# ENERGIS-Display-Board-1_1_0.net
KiCad netlist of a schematic drawn in EAGLE
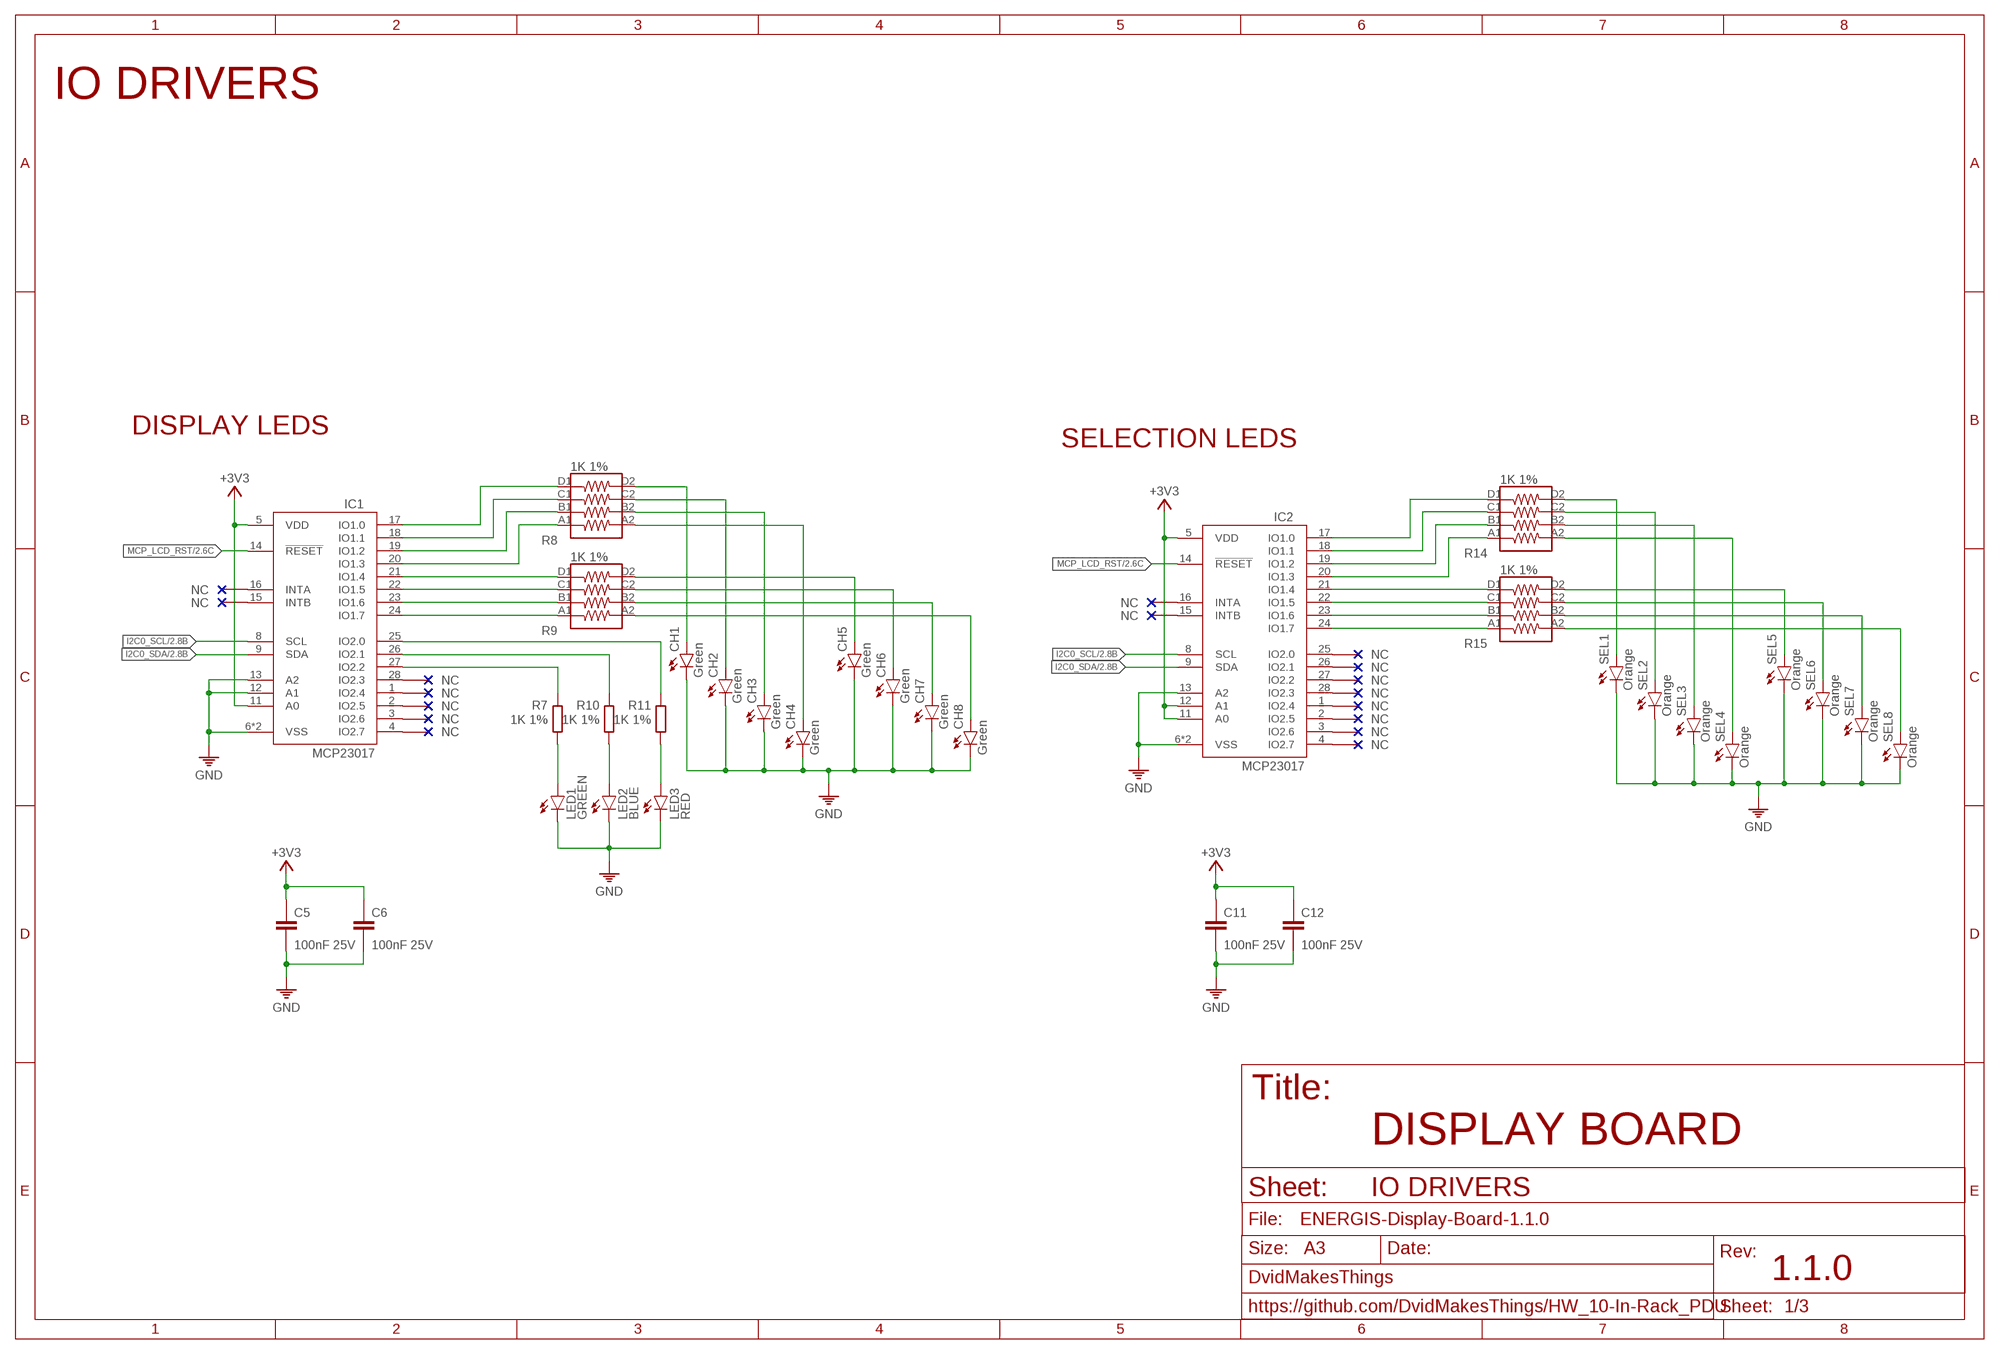
[diagram p0: schematic, sheet 1]
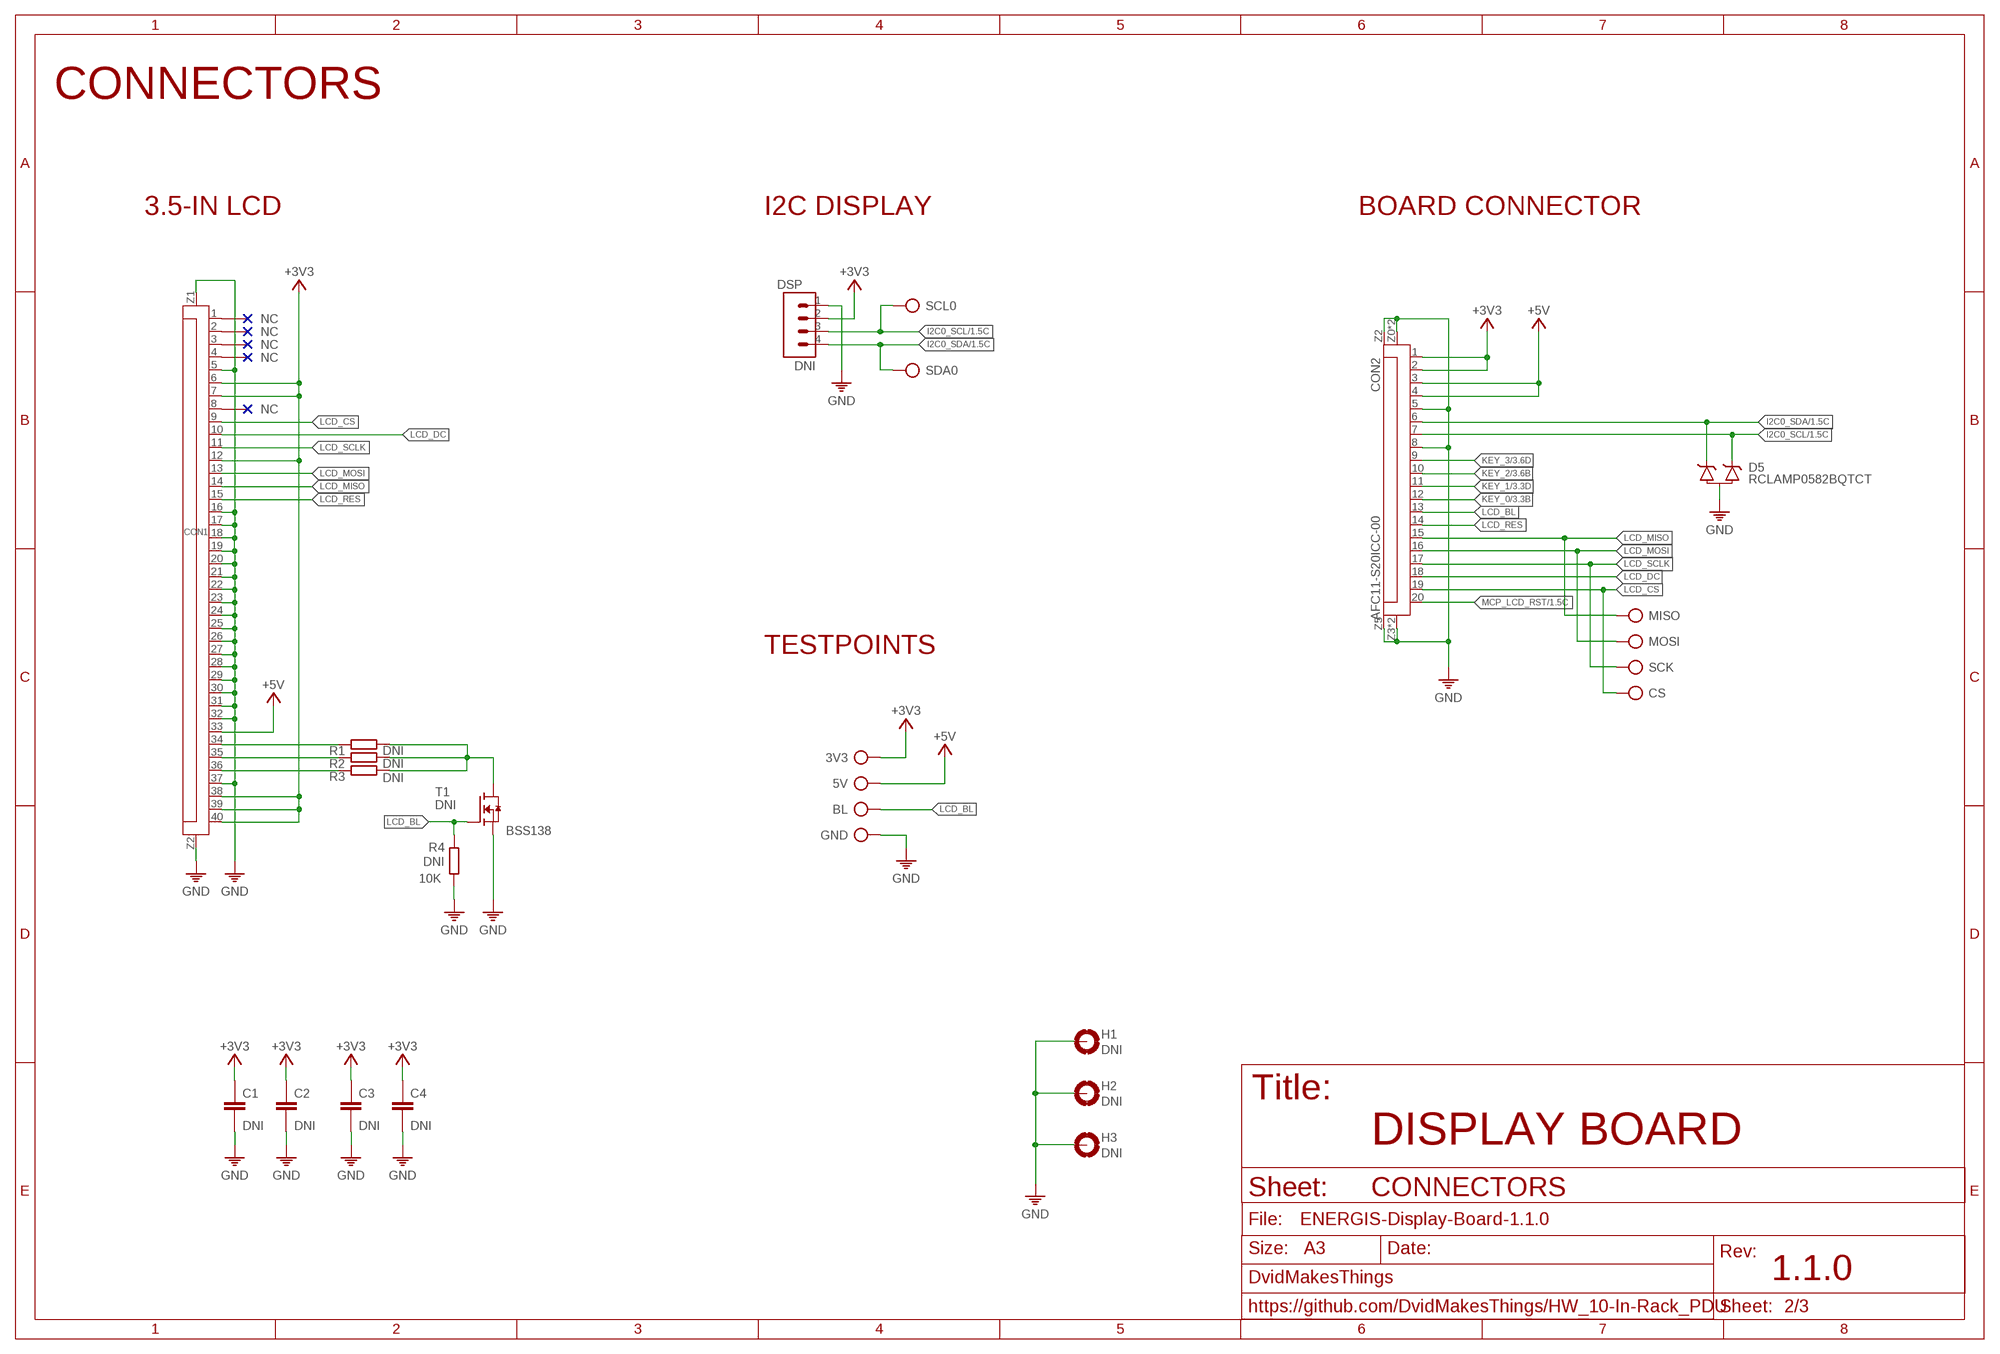
[diagram p1: schematic, sheet 2]
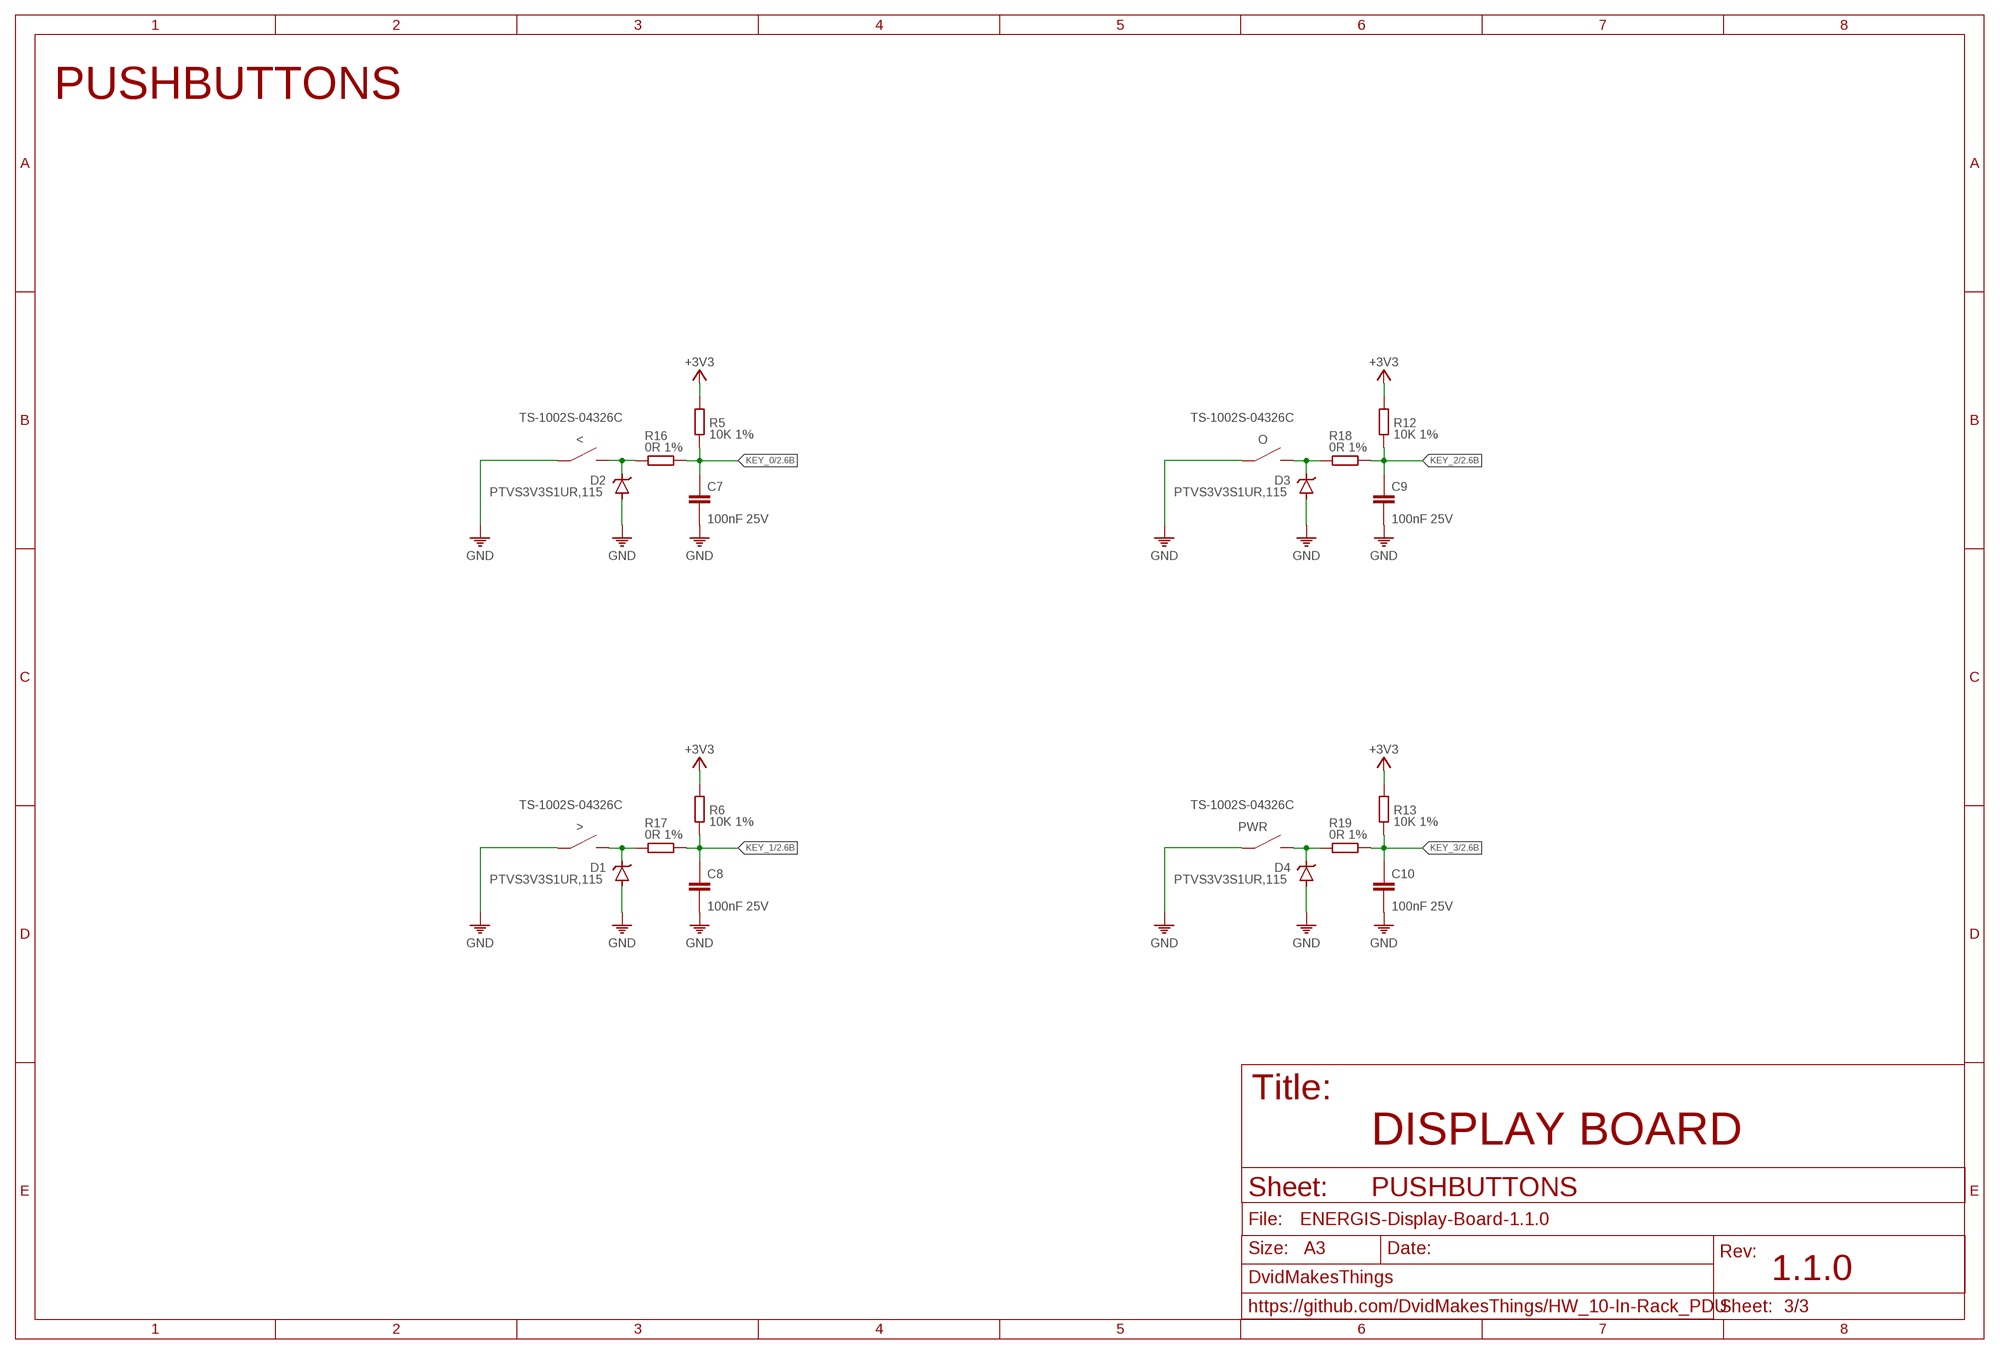
[diagram p2: schematic, sheet 3]

(export (version "E")
  (design (tool "Eeschema 10.0.6"))
  (components
    (comp (ref "C5")
      (value "100nF 25V")
      (footprint "eagle-import:0402")
      (fields
        (field (name "HQ_PART") "CA0176807")
        (field (name "LCSC_PART") "C56392")
        (field (name "MANUFACTURER") "Walsin")
      )
      (libsource (lib "eagle-import") (part "100NF-25V-0402"))
    )
    (comp (ref "C6")
      (value "100nF 25V")
      (footprint "eagle-import:0402")
      (fields
        (field (name "HQ_PART") "CA0176807")
        (field (name "LCSC_PART") "C56392")
        (field (name "MANUFACTURER") "Walsin")
      )
      (libsource (lib "eagle-import") (part "100NF-25V-0402"))
    )
    (comp (ref "C11")
      (value "100nF 25V")
      (footprint "eagle-import:0402")
      (fields
        (field (name "HQ_PART") "CA0176807")
        (field (name "LCSC_PART") "C56392")
        (field (name "MANUFACTURER") "Walsin")
      )
      (libsource (lib "eagle-import") (part "100NF-25V-0402"))
    )
    (comp (ref "C12")
      (value "100nF 25V")
      (footprint "eagle-import:0402")
      (fields
        (field (name "HQ_PART") "CA0176807")
        (field (name "LCSC_PART") "C56392")
        (field (name "MANUFACTURER") "Walsin")
      )
      (libsource (lib "eagle-import") (part "100NF-25V-0402"))
    )
    (comp (ref "CH1")
      (value "Green")
      (footprint "eagle-import:LED-0805")
      (fields
        (field (name "HQ_PART") "PH0094653")
        (field (name "LCSC_PART") "C2297")
        (field (name "MANUFACTURER") "MEIHUA")
      )
      (libsource (lib "eagle-import") (part "LED-GREENLED-0805"))
    )
    (comp (ref "CH2")
      (value "Green")
      (footprint "eagle-import:LED-0805")
      (fields
        (field (name "HQ_PART") "PH0094653")
        (field (name "LCSC_PART") "C2297")
        (field (name "MANUFACTURER") "MEIHUA")
      )
      (libsource (lib "eagle-import") (part "LED-GREENLED-0805"))
    )
    (comp (ref "CH3")
      (value "Green")
      (footprint "eagle-import:LED-0805")
      (fields
        (field (name "HQ_PART") "PH0094653")
        (field (name "LCSC_PART") "C2297")
        (field (name "MANUFACTURER") "MEIHUA")
      )
      (libsource (lib "eagle-import") (part "LED-GREENLED-0805"))
    )
    (comp (ref "CH4")
      (value "Green")
      (footprint "eagle-import:LED-0805")
      (fields
        (field (name "HQ_PART") "PH0094653")
        (field (name "LCSC_PART") "C2297")
        (field (name "MANUFACTURER") "MEIHUA")
      )
      (libsource (lib "eagle-import") (part "LED-GREENLED-0805"))
    )
    (comp (ref "CH5")
      (value "Green")
      (footprint "eagle-import:LED-0805")
      (fields
        (field (name "HQ_PART") "PH0094653")
        (field (name "LCSC_PART") "C2297")
        (field (name "MANUFACTURER") "MEIHUA")
      )
      (libsource (lib "eagle-import") (part "LED-GREENLED-0805"))
    )
    (comp (ref "CH6")
      (value "Green")
      (footprint "eagle-import:LED-0805")
      (fields
        (field (name "HQ_PART") "PH0094653")
        (field (name "LCSC_PART") "C2297")
        (field (name "MANUFACTURER") "MEIHUA")
      )
      (libsource (lib "eagle-import") (part "LED-GREENLED-0805"))
    )
    (comp (ref "CH7")
      (value "Green")
      (footprint "eagle-import:LED-0805")
      (fields
        (field (name "HQ_PART") "PH0094653")
        (field (name "LCSC_PART") "C2297")
        (field (name "MANUFACTURER") "MEIHUA")
      )
      (libsource (lib "eagle-import") (part "LED-GREENLED-0805"))
    )
    (comp (ref "CH8")
      (value "Green")
      (footprint "eagle-import:LED-0805")
      (fields
        (field (name "HQ_PART") "PH0094653")
        (field (name "LCSC_PART") "C2297")
        (field (name "MANUFACTURER") "MEIHUA")
      )
      (libsource (lib "eagle-import") (part "LED-GREENLED-0805"))
    )
    (comp (ref "IC1")
      (value "MCP23017T-E/ML")
      (footprint "eagle-import:QFN28[6X6]ML")
      (fields
        (field (name "HQ_PART") "IC0080215")
        (field (name "LCSC_PART") "C629439")
        (field (name "MANUFACTURER") "MICROCHIP")
      )
      (libsource (lib "eagle-import") (part "MCP23017-E/ML"))
    )
    (comp (ref "IC2")
      (value "MCP23017T-E/ML")
      (footprint "eagle-import:QFN28[6X6]ML")
      (fields
        (field (name "HQ_PART") "IC0080215")
        (field (name "LCSC_PART") "C629439")
        (field (name "MANUFACTURER") "MICROCHIP")
      )
      (libsource (lib "eagle-import") (part "MCP23017-E/ML"))
    )
    (comp (ref "LED1")
      (value "GREEN")
      (footprint "eagle-import:LED3MM")
      (fields
        (field (name "HQ_PART") "PH0094890")
        (field (name "LCSC_PART") "C414645")
        (field (name "MANUFACTURER") "MEIHUA")
      )
      (libsource (lib "eagle-import") (part "LED-GREEN3MM-CLEAR"))
    )
    (comp (ref "LED2")
      (value "BLUE")
      (footprint "eagle-import:LED3MM")
      (fields
        (field (name "HQ_PART") "PH0094706")
        (field (name "LCSC_PART") "C86881")
        (field (name "MANUFACTURER") "MEIHUA")
      )
      (libsource (lib "eagle-import") (part "LED-BLUE3MM-CLEAR"))
    )
    (comp (ref "LED3")
      (value "RED")
      (footprint "eagle-import:LED3MM")
      (fields
        (field (name "HQ_PART") "PH0094690")
        (field (name "LCSC_PART") "C330752")
        (field (name "MANUFACTURER") "MEIHUA")
      )
      (libsource (lib "eagle-import") (part "LED-RED3MM-CLEAR"))
    )
    (comp (ref "R7")
      (value "1K 1%")
      (footprint "eagle-import:0402")
      (fields
        (field (name "HQ_PART") "RE0208724")
        (field (name "LCSC_PART") "C11702")
        (field (name "MANUFACTURER") "FH")
      )
      (libsource (lib "eagle-import") (part "1K-1%0402"))
    )
    (comp (ref "R8")
      (value "1K 1%")
      (footprint "eagle-import:_0603X4-1206")
      (fields
        (field (name "HQ_PART") "RE0022532")
        (field (name "LCSC_PART") "C110021")
        (field (name "MANUFACTURER") "Yageo")
      )
      (libsource (lib "eagle-import") (part "1K-1%_ARRAY0603X4-1206"))
    )
    (comp (ref "R9")
      (value "1K 1%")
      (footprint "eagle-import:_0603X4-1206")
      (fields
        (field (name "HQ_PART") "RE0022532")
        (field (name "LCSC_PART") "C110021")
        (field (name "MANUFACTURER") "Yageo")
      )
      (libsource (lib "eagle-import") (part "1K-1%_ARRAY0603X4-1206"))
    )
    (comp (ref "R10")
      (value "1K 1%")
      (footprint "eagle-import:0402")
      (fields
        (field (name "HQ_PART") "RE0208724")
        (field (name "LCSC_PART") "C11702")
        (field (name "MANUFACTURER") "FH")
      )
      (libsource (lib "eagle-import") (part "1K-1%0402"))
    )
    (comp (ref "R11")
      (value "1K 1%")
      (footprint "eagle-import:0402")
      (fields
        (field (name "HQ_PART") "RE0208724")
        (field (name "LCSC_PART") "C11702")
        (field (name "MANUFACTURER") "FH")
      )
      (libsource (lib "eagle-import") (part "1K-1%0402"))
    )
    (comp (ref "R14")
      (value "1K 1%")
      (footprint "eagle-import:_0603X4-1206")
      (fields
        (field (name "HQ_PART") "RE0022532")
        (field (name "LCSC_PART") "C110021")
        (field (name "MANUFACTURER") "Yageo")
      )
      (libsource (lib "eagle-import") (part "1K-1%_ARRAY0603X4-1206"))
    )
    (comp (ref "R15")
      (value "1K 1%")
      (footprint "eagle-import:_0603X4-1206")
      (fields
        (field (name "HQ_PART") "RE0022532")
        (field (name "LCSC_PART") "C110021")
        (field (name "MANUFACTURER") "Yageo")
      )
      (libsource (lib "eagle-import") (part "1K-1%_ARRAY0603X4-1206"))
    )
    (comp (ref "SEL1")
      (value "Orange")
      (footprint "eagle-import:LED-0805")
      (fields
        (field (name "HQ_PART") "PH0093712")
        (field (name "LCSC_PART") "C434437")
        (field (name "MANUFACTURER") "NATIONSTAR")
      )
      (libsource (lib "eagle-import") (part "LED-ORANGELED-0805"))
    )
    (comp (ref "SEL2")
      (value "Orange")
      (footprint "eagle-import:LED-0805")
      (fields
        (field (name "HQ_PART") "PH0093712")
        (field (name "LCSC_PART") "C434437")
        (field (name "MANUFACTURER") "NATIONSTAR")
      )
      (libsource (lib "eagle-import") (part "LED-ORANGELED-0805"))
    )
    (comp (ref "SEL3")
      (value "Orange")
      (footprint "eagle-import:LED-0805")
      (fields
        (field (name "HQ_PART") "PH0093712")
        (field (name "LCSC_PART") "C434437")
        (field (name "MANUFACTURER") "NATIONSTAR")
      )
      (libsource (lib "eagle-import") (part "LED-ORANGELED-0805"))
    )
    (comp (ref "SEL4")
      (value "Orange")
      (footprint "eagle-import:LED-0805")
      (fields
        (field (name "HQ_PART") "PH0093712")
        (field (name "LCSC_PART") "C434437")
        (field (name "MANUFACTURER") "NATIONSTAR")
      )
      (libsource (lib "eagle-import") (part "LED-ORANGELED-0805"))
    )
    (comp (ref "SEL5")
      (value "Orange")
      (footprint "eagle-import:LED-0805")
      (fields
        (field (name "HQ_PART") "PH0093712")
        (field (name "LCSC_PART") "C434437")
        (field (name "MANUFACTURER") "NATIONSTAR")
      )
      (libsource (lib "eagle-import") (part "LED-ORANGELED-0805"))
    )
    (comp (ref "SEL6")
      (value "Orange")
      (footprint "eagle-import:LED-0805")
      (fields
        (field (name "HQ_PART") "PH0093712")
        (field (name "LCSC_PART") "C434437")
        (field (name "MANUFACTURER") "NATIONSTAR")
      )
      (libsource (lib "eagle-import") (part "LED-ORANGELED-0805"))
    )
    (comp (ref "SEL7")
      (value "Orange")
      (footprint "eagle-import:LED-0805")
      (fields
        (field (name "HQ_PART") "PH0093712")
        (field (name "LCSC_PART") "C434437")
        (field (name "MANUFACTURER") "NATIONSTAR")
      )
      (libsource (lib "eagle-import") (part "LED-ORANGELED-0805"))
    )
    (comp (ref "SEL8")
      (value "Orange")
      (footprint "eagle-import:LED-0805")
      (fields
        (field (name "HQ_PART") "PH0093712")
        (field (name "LCSC_PART") "C434437")
        (field (name "MANUFACTURER") "NATIONSTAR")
      )
      (libsource (lib "eagle-import") (part "LED-ORANGELED-0805"))
    )
    (comp (ref "3V3")
      (value "DNI")
      (footprint "eagle-import:TP-ROUND")
      (libsource (lib "eagle-import") (part "TP-ROUND"))
    )
    (comp (ref "5V")
      (value "DNI")
      (footprint "eagle-import:TP-ROUND")
      (libsource (lib "eagle-import") (part "TP-ROUND"))
    )
    (comp (ref "BL")
      (value "DNI")
      (footprint "eagle-import:TP-ROUND")
      (libsource (lib "eagle-import") (part "TP-ROUND"))
    )
    (comp (ref "C1")
      (value "DNI")
      (footprint "eagle-import:C0402")
      (libsource (lib "eagle-import") (part "C-0402"))
    )
    (comp (ref "C2")
      (value "DNI")
      (footprint "eagle-import:C0402")
      (libsource (lib "eagle-import") (part "C-0402"))
    )
    (comp (ref "C3")
      (value "DNI")
      (footprint "eagle-import:C0402")
      (libsource (lib "eagle-import") (part "C-0402"))
    )
    (comp (ref "C4")
      (value "DNI")
      (footprint "eagle-import:C0402")
      (libsource (lib "eagle-import") (part "C-0402"))
    )
    (comp (ref "CON1")
      (value "DNI")
      (footprint "eagle-import:FPC40_3.5TFT")
      (libsource (lib "eagle-import") (part "FPC40-HD"))
    )
    (comp (ref "CON2")
      (value "AFC11-S20ICC-00")
      (footprint "eagle-import:FPC20")
      (fields
        (field (name "HQ_PART") "CO0889517")
        (field (name "LCSC_PART") "C11073")
        (field (name "MANUFACTURER") "JS")
      )
      (libsource (lib "eagle-import") (part "AFC11-S20ICC-00"))
    )
    (comp (ref "CS")
      (value "DNI")
      (footprint "eagle-import:TP-ROUND")
      (libsource (lib "eagle-import") (part "TP-ROUND"))
    )
    (comp (ref "D5")
      (value "RCLAMP0582BQTCT")
      (footprint "eagle-import:SC75")
      (fields
        (field (name "HQ_PART") "PD0007296")
        (field (name "LCSC_PART") "C841193")
        (field (name "MANUFACTURER") "SEMTECH")
      )
      (libsource (lib "eagle-import") (part "RCLAMP0582BQTCT-"))
    )
    (comp (ref "DSP")
      (value "DNI")
      (footprint "eagle-import:1X4")
      (libsource (lib "eagle-import") (part "CON-1X4"))
    )
    (comp (ref "GND")
      (value "DNI")
      (footprint "eagle-import:TP-ROUND")
      (libsource (lib "eagle-import") (part "TP-ROUND"))
    )
    (comp (ref "H1")
      (value "DNI")
      (footprint "eagle-import:3,2-PAD")
      (libsource (lib "eagle-import") (part "MOUNT-PAD-ROUND3.2"))
    )
    (comp (ref "H2")
      (value "DNI")
      (footprint "eagle-import:3,2-PAD")
      (libsource (lib "eagle-import") (part "MOUNT-PAD-ROUND3.2"))
    )
    (comp (ref "H3")
      (value "DNI")
      (footprint "eagle-import:3,2-PAD")
      (libsource (lib "eagle-import") (part "MOUNT-PAD-ROUND3.2"))
    )
    (comp (ref "MISO")
      (value "DNI")
      (footprint "eagle-import:TP-ROUND")
      (libsource (lib "eagle-import") (part "TP-ROUND"))
    )
    (comp (ref "MOSI")
      (value "DNI")
      (footprint "eagle-import:TP-ROUND")
      (libsource (lib "eagle-import") (part "TP-ROUND"))
    )
    (comp (ref "R1")
      (value "DNI")
      (footprint "eagle-import:0402")
      (libsource (lib "eagle-import") (part "R0402"))
    )
    (comp (ref "R2")
      (value "DNI")
      (footprint "eagle-import:0402")
      (libsource (lib "eagle-import") (part "R0402"))
    )
    (comp (ref "R3")
      (value "DNI")
      (footprint "eagle-import:0402")
      (libsource (lib "eagle-import") (part "R0402"))
    )
    (comp (ref "R4")
      (value "DNI")
      (footprint "eagle-import:0402")
      (fields
        (field (name "HQ_PART") "RE0207399")
        (field (name "LCSC_PART") "C25744")
        (field (name "MANUFACTURER") "ROHM")
      )
      (libsource (lib "eagle-import") (part "10K-1%0402"))
    )
    (comp (ref "SCK")
      (value "DNI")
      (footprint "eagle-import:TP-ROUND")
      (libsource (lib "eagle-import") (part "TP-ROUND"))
    )
    (comp (ref "SCL0")
      (value "DNI")
      (footprint "eagle-import:TP-ROUND")
      (libsource (lib "eagle-import") (part "TP-ROUND"))
    )
    (comp (ref "SDA0")
      (value "DNI")
      (footprint "eagle-import:TP-ROUND")
      (libsource (lib "eagle-import") (part "TP-ROUND"))
    )
    (comp (ref "T1")
      (value "DNI")
      (footprint "eagle-import:SOT23")
      (fields
        (field (name "HQ_PART") "DS0190318")
        (field (name "MANUFACTURER") "HUASHUO")
        (field (name "MPN") "BSS138")
      )
      (libsource (lib "eagle-import") (part "BSS138"))
    )
    (comp (ref "<")
      (value "TS-1002S-04326C")
      (footprint "eagle-import:PUSHBUTTON-6X6")
      (fields
        (field (name "HQ_PART") "SW0049370")
        (field (name "LCSC_PART") "C455108")
        (field (name "MANUFACTURER") "USAKRO")
      )
      (libsource (lib "eagle-import") (part "SWITCH6X6-SHORT"))
    )
    (comp (ref ">")
      (value "TS-1002S-04326C")
      (footprint "eagle-import:PUSHBUTTON-6X6")
      (fields
        (field (name "HQ_PART") "SW0049370")
        (field (name "LCSC_PART") "C455108")
        (field (name "MANUFACTURER") "USAKRO")
      )
      (libsource (lib "eagle-import") (part "SWITCH6X6-SHORT"))
    )
    (comp (ref "C7")
      (value "100nF 25V")
      (footprint "eagle-import:0402")
      (fields
        (field (name "HQ_PART") "CA0176807")
        (field (name "LCSC_PART") "C56392")
        (field (name "MANUFACTURER") "Walsin")
      )
      (libsource (lib "eagle-import") (part "100NF-25V-0402"))
    )
    (comp (ref "C8")
      (value "100nF 25V")
      (footprint "eagle-import:0402")
      (fields
        (field (name "HQ_PART") "CA0176807")
        (field (name "LCSC_PART") "C56392")
        (field (name "MANUFACTURER") "Walsin")
      )
      (libsource (lib "eagle-import") (part "100NF-25V-0402"))
    )
    (comp (ref "C9")
      (value "100nF 25V")
      (footprint "eagle-import:0402")
      (fields
        (field (name "HQ_PART") "CA0176807")
        (field (name "LCSC_PART") "C56392")
        (field (name "MANUFACTURER") "Walsin")
      )
      (libsource (lib "eagle-import") (part "100NF-25V-0402"))
    )
    (comp (ref "C10")
      (value "100nF 25V")
      (footprint "eagle-import:0402")
      (fields
        (field (name "HQ_PART") "CA0176807")
        (field (name "LCSC_PART") "C56392")
        (field (name "MANUFACTURER") "Walsin")
      )
      (libsource (lib "eagle-import") (part "100NF-25V-0402"))
    )
    (comp (ref "D1")
      (value "PTVS3V3S1UR,115")
      (footprint "eagle-import:SOD-123")
      (fields
        (field (name "HQ_PART") "CP0009318")
        (field (name "LCSC_PART") "C183521")
        (field (name "MANUFACTURER") "Nexperia")
      )
      (libsource (lib "eagle-import") (part "PTVS3V3S1UR,115"))
    )
    (comp (ref "D2")
      (value "PTVS3V3S1UR,115")
      (footprint "eagle-import:SOD-123")
      (fields
        (field (name "HQ_PART") "CP0009318")
        (field (name "LCSC_PART") "C183521")
        (field (name "MANUFACTURER") "Nexperia")
      )
      (libsource (lib "eagle-import") (part "PTVS3V3S1UR,115"))
    )
    (comp (ref "D3")
      (value "PTVS3V3S1UR,115")
      (footprint "eagle-import:SOD-123")
      (fields
        (field (name "HQ_PART") "CP0009318")
        (field (name "LCSC_PART") "C183521")
        (field (name "MANUFACTURER") "Nexperia")
      )
      (libsource (lib "eagle-import") (part "PTVS3V3S1UR,115"))
    )
    (comp (ref "D4")
      (value "PTVS3V3S1UR,115")
      (footprint "eagle-import:SOD-123")
      (fields
        (field (name "HQ_PART") "CP0009318")
        (field (name "LCSC_PART") "C183521")
        (field (name "MANUFACTURER") "Nexperia")
      )
      (libsource (lib "eagle-import") (part "PTVS3V3S1UR,115"))
    )
    (comp (ref "O")
      (value "TS-1002S-04326C")
      (footprint "eagle-import:PUSHBUTTON-6X6")
      (fields
        (field (name "HQ_PART") "SW0049370")
        (field (name "LCSC_PART") "C455108")
        (field (name "MANUFACTURER") "USAKRO")
      )
      (libsource (lib "eagle-import") (part "SWITCH6X6-SHORT"))
    )
    (comp (ref "PWR")
      (value "TS-1002S-04326C")
      (footprint "eagle-import:PUSHBUTTON-6X6")
      (fields
        (field (name "HQ_PART") "SW0049370")
        (field (name "LCSC_PART") "C455108")
        (field (name "MANUFACTURER") "USAKRO")
      )
      (libsource (lib "eagle-import") (part "SWITCH6X6-SHORT"))
    )
    (comp (ref "R5")
      (value "10K 1%")
      (footprint "eagle-import:0402")
      (fields
        (field (name "HQ_PART") "RE0207399")
        (field (name "LCSC_PART") "C25744")
        (field (name "MANUFACTURER") "ROHM")
      )
      (libsource (lib "eagle-import") (part "10K-1%0402"))
    )
    (comp (ref "R6")
      (value "10K 1%")
      (footprint "eagle-import:0402")
      (fields
        (field (name "HQ_PART") "RE0207399")
        (field (name "LCSC_PART") "C25744")
        (field (name "MANUFACTURER") "ROHM")
      )
      (libsource (lib "eagle-import") (part "10K-1%0402"))
    )
    (comp (ref "R12")
      (value "10K 1%")
      (footprint "eagle-import:0402")
      (fields
        (field (name "HQ_PART") "RE0207399")
        (field (name "LCSC_PART") "C25744")
        (field (name "MANUFACTURER") "ROHM")
      )
      (libsource (lib "eagle-import") (part "10K-1%0402"))
    )
    (comp (ref "R13")
      (value "10K 1%")
      (footprint "eagle-import:0402")
      (fields
        (field (name "HQ_PART") "RE0207399")
        (field (name "LCSC_PART") "C25744")
        (field (name "MANUFACTURER") "ROHM")
      )
      (libsource (lib "eagle-import") (part "10K-1%0402"))
    )
    (comp (ref "R16")
      (value "0R 1%")
      (footprint "eagle-import:0402")
      (fields
        (field (name "HQ_PART") "RE0250181")
        (field (name "LCSC_PART") "C17168")
        (field (name "MANUFACTURER") "YAGEO")
      )
      (libsource (lib "eagle-import") (part "0R0402"))
    )
    (comp (ref "R17")
      (value "0R 1%")
      (footprint "eagle-import:0402")
      (fields
        (field (name "HQ_PART") "RE0250181")
        (field (name "LCSC_PART") "C17168")
        (field (name "MANUFACTURER") "YAGEO")
      )
      (libsource (lib "eagle-import") (part "0R0402"))
    )
    (comp (ref "R18")
      (value "0R 1%")
      (footprint "eagle-import:0402")
      (fields
        (field (name "HQ_PART") "RE0250181")
        (field (name "LCSC_PART") "C17168")
        (field (name "MANUFACTURER") "YAGEO")
      )
      (libsource (lib "eagle-import") (part "0R0402"))
    )
    (comp (ref "R19")
      (value "0R 1%")
      (footprint "eagle-import:0402")
      (fields
        (field (name "HQ_PART") "RE0250181")
        (field (name "LCSC_PART") "C17168")
        (field (name "MANUFACTURER") "YAGEO")
      )
      (libsource (lib "eagle-import") (part "0R0402"))
    )
  )
  (nets
    (net (code "1") (name "+3V3") (class "Default")
      (node (ref "3V3") (pin "TP") (pinfunction "P$1_TP") (pintype "bidirectional"))
      (node (ref "C1") (pin "1") (pinfunction "1_1") (pintype "passive"))
      (node (ref "C11") (pin "1") (pinfunction "1_1") (pintype "passive"))
      (node (ref "C12") (pin "1") (pinfunction "1_1") (pintype "passive"))
      (node (ref "C2") (pin "1") (pinfunction "1_1") (pintype "passive"))
      (node (ref "C3") (pin "1") (pinfunction "1_1") (pintype "passive"))
      (node (ref "C4") (pin "1") (pinfunction "1_1") (pintype "passive"))
      (node (ref "C5") (pin "1") (pinfunction "1_1") (pintype "passive"))
      (node (ref "C6") (pin "1") (pinfunction "1_1") (pintype "passive"))
      (node (ref "CON1") (pin "12") (pinfunction "12_12") (pintype "bidirectional"))
      (node (ref "CON1") (pin "38") (pinfunction "38_38") (pintype "bidirectional"))
      (node (ref "CON1") (pin "39") (pinfunction "39_39") (pintype "bidirectional"))
      (node (ref "CON1") (pin "40") (pinfunction "40_40") (pintype "bidirectional"))
      (node (ref "CON1") (pin "6") (pinfunction "6_6") (pintype "bidirectional"))
      (node (ref "CON1") (pin "7") (pinfunction "7_7") (pintype "bidirectional"))
      (node (ref "CON2") (pin "1") (pinfunction "1_1") (pintype "bidirectional"))
      (node (ref "CON2") (pin "2") (pinfunction "2_2") (pintype "bidirectional"))
      (node (ref "DSP") (pin "2") (pinfunction "P$2_2") (pintype "bidirectional"))
      (node (ref "IC1") (pin "11") (pinfunction "A0_11") (pintype "bidirectional"))
      (node (ref "IC1") (pin "5") (pinfunction "VDD_5") (pintype "bidirectional"))
      (node (ref "IC2") (pin "11") (pinfunction "A0_11") (pintype "bidirectional"))
      (node (ref "IC2") (pin "12") (pinfunction "A1_12") (pintype "bidirectional"))
      (node (ref "IC2") (pin "5") (pinfunction "VDD_5") (pintype "bidirectional"))
      (node (ref "R12") (pin "1") (pinfunction "1_1") (pintype "passive"))
      (node (ref "R13") (pin "1") (pinfunction "1_1") (pintype "passive"))
      (node (ref "R5") (pin "1") (pinfunction "1_1") (pintype "passive"))
      (node (ref "R6") (pin "1") (pinfunction "1_1") (pintype "passive"))
    )
    (net (code "2") (name "+5V") (class "Default")
      (node (ref "5V") (pin "TP") (pinfunction "P$1_TP") (pintype "bidirectional"))
      (node (ref "CON1") (pin "33") (pinfunction "33_33") (pintype "bidirectional"))
      (node (ref "CON2") (pin "3") (pinfunction "3_3") (pintype "bidirectional"))
      (node (ref "CON2") (pin "4") (pinfunction "4_4") (pintype "bidirectional"))
    )
    (net (code "3") (name "GND") (class "Default")
      (node (ref "<") (pin "1") (pinfunction "P$1_1") (pintype "bidirectional"))
      (node (ref "<") (pin "2") (pinfunction "P$1_2") (pintype "bidirectional"))
      (node (ref ">") (pin "1") (pinfunction "P$1_1") (pintype "bidirectional"))
      (node (ref ">") (pin "2") (pinfunction "P$1_2") (pintype "bidirectional"))
      (node (ref "C1") (pin "2") (pinfunction "2_2") (pintype "passive"))
      (node (ref "C10") (pin "2") (pinfunction "2_2") (pintype "passive"))
      (node (ref "C11") (pin "2") (pinfunction "2_2") (pintype "passive"))
      (node (ref "C12") (pin "2") (pinfunction "2_2") (pintype "passive"))
      (node (ref "C2") (pin "2") (pinfunction "2_2") (pintype "passive"))
      (node (ref "C3") (pin "2") (pinfunction "2_2") (pintype "passive"))
      (node (ref "C4") (pin "2") (pinfunction "2_2") (pintype "passive"))
      (node (ref "C5") (pin "2") (pinfunction "2_2") (pintype "passive"))
      (node (ref "C6") (pin "2") (pinfunction "2_2") (pintype "passive"))
      (node (ref "C7") (pin "2") (pinfunction "2_2") (pintype "passive"))
      (node (ref "C8") (pin "2") (pinfunction "2_2") (pintype "passive"))
      (node (ref "C9") (pin "2") (pinfunction "2_2") (pintype "passive"))
      (node (ref "CH1") (pin "C") (pinfunction "C_C") (pintype "passive"))
      (node (ref "CH2") (pin "C") (pinfunction "C_C") (pintype "passive"))
      (node (ref "CH3") (pin "C") (pinfunction "C_C") (pintype "passive"))
      (node (ref "CH4") (pin "C") (pinfunction "C_C") (pintype "passive"))
      (node (ref "CH5") (pin "C") (pinfunction "C_C") (pintype "passive"))
      (node (ref "CH6") (pin "C") (pinfunction "C_C") (pintype "passive"))
      (node (ref "CH7") (pin "C") (pinfunction "C_C") (pintype "passive"))
      (node (ref "CH8") (pin "C") (pinfunction "C_C") (pintype "passive"))
      (node (ref "CON1") (pin "16") (pinfunction "16_16") (pintype "bidirectional"))
      (node (ref "CON1") (pin "17") (pinfunction "17_17") (pintype "bidirectional"))
      (node (ref "CON1") (pin "18") (pinfunction "18_18") (pintype "bidirectional"))
      (node (ref "CON1") (pin "19") (pinfunction "19_19") (pintype "bidirectional"))
      (node (ref "CON1") (pin "20") (pinfunction "20_20") (pintype "bidirectional"))
      (node (ref "CON1") (pin "21") (pinfunction "21_21") (pintype "bidirectional"))
      (node (ref "CON1") (pin "22") (pinfunction "22_22") (pintype "bidirectional"))
      (node (ref "CON1") (pin "23") (pinfunction "23_23") (pintype "bidirectional"))
      (node (ref "CON1") (pin "24") (pinfunction "24_24") (pintype "bidirectional"))
      (node (ref "CON1") (pin "25") (pinfunction "25_25") (pintype "bidirectional"))
      (node (ref "CON1") (pin "26") (pinfunction "26_26") (pintype "bidirectional"))
      (node (ref "CON1") (pin "27") (pinfunction "27_27") (pintype "bidirectional"))
      (node (ref "CON1") (pin "28") (pinfunction "28_28") (pintype "bidirectional"))
      (node (ref "CON1") (pin "29") (pinfunction "29_29") (pintype "bidirectional"))
      (node (ref "CON1") (pin "30") (pinfunction "30_30") (pintype "bidirectional"))
      (node (ref "CON1") (pin "31") (pinfunction "31_31") (pintype "bidirectional"))
      (node (ref "CON1") (pin "32") (pinfunction "32_32") (pintype "bidirectional"))
      (node (ref "CON1") (pin "37") (pinfunction "37_37") (pintype "bidirectional"))
      (node (ref "CON1") (pin "5") (pinfunction "5_5") (pintype "bidirectional"))
      (node (ref "CON1") (pin "Z1") (pinfunction "Z1_Z1") (pintype "bidirectional"))
      (node (ref "CON1") (pin "Z2") (pinfunction "Z2_Z2") (pintype "bidirectional"))
      (node (ref "CON2") (pin "5") (pinfunction "5_5") (pintype "bidirectional"))
      (node (ref "CON2") (pin "8") (pinfunction "8_8") (pintype "bidirectional"))
      (node (ref "CON2") (pin "Z0") (pinfunction "Z1_Z0") (pintype "bidirectional"))
      (node (ref "CON2") (pin "Z1") (pinfunction "Z1_Z1") (pintype "bidirectional"))
      (node (ref "CON2") (pin "Z2") (pinfunction "Z2_Z2") (pintype "bidirectional"))
      (node (ref "CON2") (pin "Z3") (pinfunction "Z3_Z3") (pintype "bidirectional"))
      (node (ref "CON2") (pin "Z4") (pinfunction "Z3_Z4") (pintype "bidirectional"))
      (node (ref "CON2") (pin "Z5") (pinfunction "Z4_Z5") (pintype "bidirectional"))
      (node (ref "D1") (pin "A") (pinfunction "A_A") (pintype "passive"))
      (node (ref "D2") (pin "A") (pinfunction "A_A") (pintype "passive"))
      (node (ref "D3") (pin "A") (pinfunction "A_A") (pintype "passive"))
      (node (ref "D4") (pin "A") (pinfunction "A_A") (pintype "passive"))
      (node (ref "D5") (pin "3") (pinfunction "3_3") (pintype "bidirectional"))
      (node (ref "DSP") (pin "1") (pinfunction "P$1_1") (pintype "bidirectional"))
      (node (ref "GND") (pin "TP") (pinfunction "P$1_TP") (pintype "bidirectional"))
      (node (ref "H1") (pin "B3,2") (pinfunction "MOUNT_B3,2") (pintype "passive"))
      (node (ref "H2") (pin "B3,2") (pinfunction "MOUNT_B3,2") (pintype "passive"))
      (node (ref "H3") (pin "B3,2") (pinfunction "MOUNT_B3,2") (pintype "passive"))
      (node (ref "IC1") (pin "12") (pinfunction "A1_12") (pintype "bidirectional"))
      (node (ref "IC1") (pin "13") (pinfunction "A2_13") (pintype "bidirectional"))
      (node (ref "IC1") (pin "6") (pinfunction "VSS_6") (pintype "bidirectional"))
      (node (ref "IC1") (pin "PAD") (pinfunction "VSS_PAD") (pintype "bidirectional"))
      (node (ref "IC2") (pin "13") (pinfunction "A2_13") (pintype "bidirectional"))
      (node (ref "IC2") (pin "6") (pinfunction "VSS_6") (pintype "bidirectional"))
      (node (ref "IC2") (pin "PAD") (pinfunction "VSS_PAD") (pintype "bidirectional"))
      (node (ref "LED1") (pin "K") (pinfunction "C_K") (pintype "passive"))
      (node (ref "LED2") (pin "K") (pinfunction "C_K") (pintype "passive"))
      (node (ref "LED3") (pin "K") (pinfunction "C_K") (pintype "passive"))
      (node (ref "O") (pin "1") (pinfunction "P$1_1") (pintype "bidirectional"))
      (node (ref "O") (pin "2") (pinfunction "P$1_2") (pintype "bidirectional"))
      (node (ref "PWR") (pin "1") (pinfunction "P$1_1") (pintype "bidirectional"))
      (node (ref "PWR") (pin "2") (pinfunction "P$1_2") (pintype "bidirectional"))
      (node (ref "R4") (pin "2") (pinfunction "2_2") (pintype "passive"))
      (node (ref "SEL1") (pin "C") (pinfunction "C_C") (pintype "passive"))
      (node (ref "SEL2") (pin "C") (pinfunction "C_C") (pintype "passive"))
      (node (ref "SEL3") (pin "C") (pinfunction "C_C") (pintype "passive"))
      (node (ref "SEL4") (pin "C") (pinfunction "C_C") (pintype "passive"))
      (node (ref "SEL5") (pin "C") (pinfunction "C_C") (pintype "passive"))
      (node (ref "SEL6") (pin "C") (pinfunction "C_C") (pintype "passive"))
      (node (ref "SEL7") (pin "C") (pinfunction "C_C") (pintype "passive"))
      (node (ref "SEL8") (pin "C") (pinfunction "C_C") (pintype "passive"))
      (node (ref "T1") (pin "2") (pinfunction "S_2") (pintype "passive"))
    )
    (net (code "4") (name "I2C0_SCL") (class "Default")
      (node (ref "CON2") (pin "7") (pinfunction "7_7") (pintype "bidirectional"))
      (node (ref "D5") (pin "1") (pinfunction "1_1") (pintype "bidirectional"))
      (node (ref "DSP") (pin "3") (pinfunction "P$3_3") (pintype "bidirectional"))
      (node (ref "IC1") (pin "8") (pinfunction "SCL_8") (pintype "bidirectional"))
      (node (ref "IC2") (pin "8") (pinfunction "SCL_8") (pintype "bidirectional"))
      (node (ref "SCL0") (pin "TP") (pinfunction "P$1_TP") (pintype "bidirectional"))
    )
    (net (code "5") (name "I2C0_SDA") (class "Default")
      (node (ref "CON2") (pin "6") (pinfunction "6_6") (pintype "bidirectional"))
      (node (ref "D5") (pin "2") (pinfunction "2_2") (pintype "bidirectional"))
      (node (ref "DSP") (pin "4") (pinfunction "P$4_4") (pintype "bidirectional"))
      (node (ref "IC1") (pin "9") (pinfunction "SDA_9") (pintype "bidirectional"))
      (node (ref "IC2") (pin "9") (pinfunction "SDA_9") (pintype "bidirectional"))
      (node (ref "SDA0") (pin "TP") (pinfunction "P$1_TP") (pintype "bidirectional"))
    )
    (net (code "6") (name "KEY_0") (class "Default")
      (node (ref "C7") (pin "1") (pinfunction "1_1") (pintype "passive"))
      (node (ref "CON2") (pin "12") (pinfunction "12_12") (pintype "bidirectional"))
      (node (ref "R16") (pin "2") (pinfunction "2_2") (pintype "passive"))
      (node (ref "R5") (pin "2") (pinfunction "2_2") (pintype "passive"))
    )
    (net (code "7") (name "KEY_1") (class "Default")
      (node (ref "C8") (pin "1") (pinfunction "1_1") (pintype "passive"))
      (node (ref "CON2") (pin "11") (pinfunction "11_11") (pintype "bidirectional"))
      (node (ref "R17") (pin "2") (pinfunction "2_2") (pintype "passive"))
      (node (ref "R6") (pin "2") (pinfunction "2_2") (pintype "passive"))
    )
    (net (code "8") (name "KEY_2") (class "Default")
      (node (ref "C9") (pin "1") (pinfunction "1_1") (pintype "passive"))
      (node (ref "CON2") (pin "10") (pinfunction "10_10") (pintype "bidirectional"))
      (node (ref "R12") (pin "2") (pinfunction "2_2") (pintype "passive"))
      (node (ref "R18") (pin "2") (pinfunction "2_2") (pintype "passive"))
    )
    (net (code "9") (name "KEY_3") (class "Default")
      (node (ref "C10") (pin "1") (pinfunction "1_1") (pintype "passive"))
      (node (ref "CON2") (pin "9") (pinfunction "9_9") (pintype "bidirectional"))
      (node (ref "R13") (pin "2") (pinfunction "2_2") (pintype "passive"))
      (node (ref "R19") (pin "2") (pinfunction "2_2") (pintype "passive"))
    )
    (net (code "10") (name "LCD_BL") (class "Default")
      (node (ref "BL") (pin "TP") (pinfunction "P$1_TP") (pintype "bidirectional"))
      (node (ref "CON2") (pin "13") (pinfunction "13_13") (pintype "bidirectional"))
      (node (ref "R4") (pin "1") (pinfunction "1_1") (pintype "passive"))
      (node (ref "T1") (pin "1") (pinfunction "G_1") (pintype "passive"))
    )
    (net (code "11") (name "LCD_CS") (class "Default")
      (node (ref "CON1") (pin "9") (pinfunction "9_9") (pintype "bidirectional"))
      (node (ref "CON2") (pin "19") (pinfunction "19_19") (pintype "bidirectional"))
      (node (ref "CS") (pin "TP") (pinfunction "P$1_TP") (pintype "bidirectional"))
    )
    (net (code "12") (name "LCD_DC") (class "Default")
      (node (ref "CON1") (pin "10") (pinfunction "10_10") (pintype "bidirectional"))
      (node (ref "CON2") (pin "18") (pinfunction "18_18") (pintype "bidirectional"))
    )
    (net (code "13") (name "LCD_MISO") (class "Default")
      (node (ref "CON1") (pin "14") (pinfunction "14_14") (pintype "bidirectional"))
      (node (ref "CON2") (pin "15") (pinfunction "15_15") (pintype "bidirectional"))
      (node (ref "MISO") (pin "TP") (pinfunction "P$1_TP") (pintype "bidirectional"))
    )
    (net (code "14") (name "LCD_MOSI") (class "Default")
      (node (ref "CON1") (pin "13") (pinfunction "13_13") (pintype "bidirectional"))
      (node (ref "CON2") (pin "16") (pinfunction "16_16") (pintype "bidirectional"))
      (node (ref "MOSI") (pin "TP") (pinfunction "P$1_TP") (pintype "bidirectional"))
    )
    (net (code "15") (name "LCD_RES") (class "Default")
      (node (ref "CON1") (pin "15") (pinfunction "15_15") (pintype "bidirectional"))
      (node (ref "CON2") (pin "14") (pinfunction "14_14") (pintype "bidirectional"))
    )
    (net (code "16") (name "LCD_SCLK") (class "Default")
      (node (ref "CON1") (pin "11") (pinfunction "11_11") (pintype "bidirectional"))
      (node (ref "CON2") (pin "17") (pinfunction "17_17") (pintype "bidirectional"))
      (node (ref "SCK") (pin "TP") (pinfunction "P$1_TP") (pintype "bidirectional"))
    )
    (net (code "17") (name "MCP_LCD_RST") (class "Default")
      (node (ref "CON2") (pin "20") (pinfunction "20_20") (pintype "bidirectional"))
      (node (ref "IC1") (pin "14") (pinfunction "~{RESET}_14") (pintype "bidirectional"))
      (node (ref "IC2") (pin "14") (pinfunction "~{RESET}_14") (pintype "bidirectional"))
    )
    (net (code "18") (name "Net-(<-P$2-Pad3)") (class "Default")
      (node (ref "<") (pin "3") (pinfunction "P$2_3") (pintype "bidirectional"))
      (node (ref "<") (pin "4") (pinfunction "P$2_4") (pintype "bidirectional"))
      (node (ref "D2") (pin "C") (pinfunction "C_C") (pintype "passive"))
      (node (ref "R16") (pin "1") (pinfunction "1_1") (pintype "passive"))
    )
    (net (code "19") (name "Net-(>-P$2-Pad3)") (class "Default")
      (node (ref ">") (pin "3") (pinfunction "P$2_3") (pintype "bidirectional"))
      (node (ref ">") (pin "4") (pinfunction "P$2_4") (pintype "bidirectional"))
      (node (ref "D1") (pin "C") (pinfunction "C_C") (pintype "passive"))
      (node (ref "R17") (pin "1") (pinfunction "1_1") (pintype "passive"))
    )
    (net (code "20") (name "Net-(CON1-Pad34)") (class "Default")
      (node (ref "CON1") (pin "34") (pinfunction "34_34") (pintype "bidirectional"))
      (node (ref "R1") (pin "2") (pinfunction "2_2") (pintype "passive"))
    )
    (net (code "21") (name "Net-(CON1-Pad35)") (class "Default")
      (node (ref "CON1") (pin "35") (pinfunction "35_35") (pintype "bidirectional"))
      (node (ref "R2") (pin "2") (pinfunction "2_2") (pintype "passive"))
    )
    (net (code "22") (name "Net-(CON1-Pad36)") (class "Default")
      (node (ref "CON1") (pin "36") (pinfunction "36_36") (pintype "bidirectional"))
      (node (ref "R3") (pin "2") (pinfunction "2_2") (pintype "passive"))
    )
    (net (code "23") (name "Net-(D3-PadC)") (class "Default")
      (node (ref "D3") (pin "C") (pinfunction "C_C") (pintype "passive"))
      (node (ref "O") (pin "3") (pinfunction "P$2_3") (pintype "bidirectional"))
      (node (ref "O") (pin "4") (pinfunction "P$2_4") (pintype "bidirectional"))
      (node (ref "R18") (pin "1") (pinfunction "1_1") (pintype "passive"))
    )
    (net (code "24") (name "Net-(D4-PadC)") (class "Default")
      (node (ref "D4") (pin "C") (pinfunction "C_C") (pintype "passive"))
      (node (ref "PWR") (pin "3") (pinfunction "P$2_3") (pintype "bidirectional"))
      (node (ref "PWR") (pin "4") (pinfunction "P$2_4") (pintype "bidirectional"))
      (node (ref "R19") (pin "1") (pinfunction "1_1") (pintype "passive"))
    )
    (net (code "25") (name "Net-(IC1-IO1.0)") (class "Default")
      (node (ref "IC1") (pin "17") (pinfunction "IO1.0_17") (pintype "bidirectional"))
      (node (ref "R8") (pin "D1") (pinfunction "4_D1") (pintype "passive"))
    )
    (net (code "26") (name "Net-(IC1-IO1.1)") (class "Default")
      (node (ref "IC1") (pin "18") (pinfunction "IO1.1_18") (pintype "bidirectional"))
      (node (ref "R8") (pin "C1") (pinfunction "3_C1") (pintype "passive"))
    )
    (net (code "27") (name "Net-(IC1-IO1.2)") (class "Default")
      (node (ref "IC1") (pin "19") (pinfunction "IO1.2_19") (pintype "bidirectional"))
      (node (ref "R8") (pin "B1") (pinfunction "2_B1") (pintype "passive"))
    )
    (net (code "28") (name "Net-(IC1-IO1.3)") (class "Default")
      (node (ref "IC1") (pin "20") (pinfunction "IO1.3_20") (pintype "bidirectional"))
      (node (ref "R8") (pin "A1") (pinfunction "1_A1") (pintype "passive"))
    )
    (net (code "29") (name "Net-(IC1-IO1.4)") (class "Default")
      (node (ref "IC1") (pin "21") (pinfunction "IO1.4_21") (pintype "bidirectional"))
      (node (ref "R9") (pin "D1") (pinfunction "4_D1") (pintype "passive"))
    )
    (net (code "30") (name "Net-(IC1-IO1.5)") (class "Default")
      (node (ref "IC1") (pin "22") (pinfunction "IO1.5_22") (pintype "bidirectional"))
      (node (ref "R9") (pin "C1") (pinfunction "3_C1") (pintype "passive"))
    )
    (net (code "31") (name "Net-(IC1-IO1.6)") (class "Default")
      (node (ref "IC1") (pin "23") (pinfunction "IO1.6_23") (pintype "bidirectional"))
      (node (ref "R9") (pin "B1") (pinfunction "2_B1") (pintype "passive"))
    )
    (net (code "32") (name "Net-(IC1-IO1.7)") (class "Default")
      (node (ref "IC1") (pin "24") (pinfunction "IO1.7_24") (pintype "bidirectional"))
      (node (ref "R9") (pin "A1") (pinfunction "1_A1") (pintype "passive"))
    )
    (net (code "33") (name "Net-(IC1-IO2.0)") (class "Default")
      (node (ref "IC1") (pin "25") (pinfunction "IO2.0_25") (pintype "bidirectional"))
      (node (ref "R11") (pin "1") (pinfunction "1_1") (pintype "passive"))
    )
    (net (code "34") (name "Net-(IC1-IO2.1)") (class "Default")
      (node (ref "IC1") (pin "26") (pinfunction "IO2.1_26") (pintype "bidirectional"))
      (node (ref "R10") (pin "1") (pinfunction "1_1") (pintype "passive"))
    )
    (net (code "35") (name "Net-(IC1-IO2.2)") (class "Default")
      (node (ref "IC1") (pin "27") (pinfunction "IO2.2_27") (pintype "bidirectional"))
      (node (ref "R7") (pin "1") (pinfunction "1_1") (pintype "passive"))
    )
    (net (code "36") (name "Net-(IC2-IO1.0)") (class "Default")
      (node (ref "IC2") (pin "17") (pinfunction "IO1.0_17") (pintype "bidirectional"))
      (node (ref "R14") (pin "D1") (pinfunction "4_D1") (pintype "passive"))
    )
    (net (code "37") (name "Net-(IC2-IO1.1)") (class "Default")
      (node (ref "IC2") (pin "18") (pinfunction "IO1.1_18") (pintype "bidirectional"))
      (node (ref "R14") (pin "C1") (pinfunction "3_C1") (pintype "passive"))
    )
    (net (code "38") (name "Net-(IC2-IO1.2)") (class "Default")
      (node (ref "IC2") (pin "19") (pinfunction "IO1.2_19") (pintype "bidirectional"))
      (node (ref "R14") (pin "B1") (pinfunction "2_B1") (pintype "passive"))
    )
    (net (code "39") (name "Net-(IC2-IO1.3)") (class "Default")
      (node (ref "IC2") (pin "20") (pinfunction "IO1.3_20") (pintype "bidirectional"))
      (node (ref "R14") (pin "A1") (pinfunction "1_A1") (pintype "passive"))
    )
    (net (code "40") (name "Net-(IC2-IO1.4)") (class "Default")
      (node (ref "IC2") (pin "21") (pinfunction "IO1.4_21") (pintype "bidirectional"))
      (node (ref "R15") (pin "D1") (pinfunction "4_D1") (pintype "passive"))
    )
    (net (code "41") (name "Net-(IC2-IO1.5)") (class "Default")
      (node (ref "IC2") (pin "22") (pinfunction "IO1.5_22") (pintype "bidirectional"))
      (node (ref "R15") (pin "C1") (pinfunction "3_C1") (pintype "passive"))
    )
    (net (code "42") (name "Net-(IC2-IO1.6)") (class "Default")
      (node (ref "IC2") (pin "23") (pinfunction "IO1.6_23") (pintype "bidirectional"))
      (node (ref "R15") (pin "B1") (pinfunction "2_B1") (pintype "passive"))
    )
    (net (code "43") (name "Net-(IC2-IO1.7)") (class "Default")
      (node (ref "IC2") (pin "24") (pinfunction "IO1.7_24") (pintype "bidirectional"))
      (node (ref "R15") (pin "A1") (pinfunction "1_A1") (pintype "passive"))
    )
    (net (code "44") (name "Net-(LED1-PadA)") (class "Default")
      (node (ref "LED1") (pin "A") (pinfunction "A_A") (pintype "passive"))
      (node (ref "R7") (pin "2") (pinfunction "2_2") (pintype "passive"))
    )
    (net (code "45") (name "Net-(LED2-PadA)") (class "Default")
      (node (ref "LED2") (pin "A") (pinfunction "A_A") (pintype "passive"))
      (node (ref "R10") (pin "2") (pinfunction "2_2") (pintype "passive"))
    )
    (net (code "46") (name "Net-(LED3-PadA)") (class "Default")
      (node (ref "LED3") (pin "A") (pinfunction "A_A") (pintype "passive"))
      (node (ref "R11") (pin "2") (pinfunction "2_2") (pintype "passive"))
    )
    (net (code "47") (name "Net-(R8-5)") (class "Default")
      (node (ref "CH1") (pin "A") (pinfunction "A_A") (pintype "passive"))
      (node (ref "R8") (pin "D2") (pinfunction "5_D2") (pintype "passive"))
    )
    (net (code "48") (name "Net-(R8-6)") (class "Default")
      (node (ref "CH2") (pin "A") (pinfunction "A_A") (pintype "passive"))
      (node (ref "R8") (pin "C2") (pinfunction "6_C2") (pintype "passive"))
    )
    (net (code "49") (name "Net-(R8-7)") (class "Default")
      (node (ref "CH3") (pin "A") (pinfunction "A_A") (pintype "passive"))
      (node (ref "R8") (pin "B2") (pinfunction "7_B2") (pintype "passive"))
    )
    (net (code "50") (name "Net-(R8-8)") (class "Default")
      (node (ref "CH4") (pin "A") (pinfunction "A_A") (pintype "passive"))
      (node (ref "R8") (pin "A2") (pinfunction "8_A2") (pintype "passive"))
    )
    (net (code "51") (name "Net-(R9-5)") (class "Default")
      (node (ref "CH5") (pin "A") (pinfunction "A_A") (pintype "passive"))
      (node (ref "R9") (pin "D2") (pinfunction "5_D2") (pintype "passive"))
    )
    (net (code "52") (name "Net-(R9-6)") (class "Default")
      (node (ref "CH6") (pin "A") (pinfunction "A_A") (pintype "passive"))
      (node (ref "R9") (pin "C2") (pinfunction "6_C2") (pintype "passive"))
    )
    (net (code "53") (name "Net-(R9-7)") (class "Default")
      (node (ref "CH7") (pin "A") (pinfunction "A_A") (pintype "passive"))
      (node (ref "R9") (pin "B2") (pinfunction "7_B2") (pintype "passive"))
    )
    (net (code "54") (name "Net-(R9-8)") (class "Default")
      (node (ref "CH8") (pin "A") (pinfunction "A_A") (pintype "passive"))
      (node (ref "R9") (pin "A2") (pinfunction "8_A2") (pintype "passive"))
    )
    (net (code "55") (name "Net-(R14-5)") (class "Default")
      (node (ref "R14") (pin "D2") (pinfunction "5_D2") (pintype "passive"))
      (node (ref "SEL1") (pin "A") (pinfunction "A_A") (pintype "passive"))
    )
    (net (code "56") (name "Net-(R14-6)") (class "Default")
      (node (ref "R14") (pin "C2") (pinfunction "6_C2") (pintype "passive"))
      (node (ref "SEL2") (pin "A") (pinfunction "A_A") (pintype "passive"))
    )
    (net (code "57") (name "Net-(R14-7)") (class "Default")
      (node (ref "R14") (pin "B2") (pinfunction "7_B2") (pintype "passive"))
      (node (ref "SEL3") (pin "A") (pinfunction "A_A") (pintype "passive"))
    )
    (net (code "58") (name "Net-(R14-8)") (class "Default")
      (node (ref "R14") (pin "A2") (pinfunction "8_A2") (pintype "passive"))
      (node (ref "SEL4") (pin "A") (pinfunction "A_A") (pintype "passive"))
    )
    (net (code "59") (name "Net-(R15-5)") (class "Default")
      (node (ref "R15") (pin "D2") (pinfunction "5_D2") (pintype "passive"))
      (node (ref "SEL5") (pin "A") (pinfunction "A_A") (pintype "passive"))
    )
    (net (code "60") (name "Net-(R15-6)") (class "Default")
      (node (ref "R15") (pin "C2") (pinfunction "6_C2") (pintype "passive"))
      (node (ref "SEL6") (pin "A") (pinfunction "A_A") (pintype "passive"))
    )
    (net (code "61") (name "Net-(R15-7)") (class "Default")
      (node (ref "R15") (pin "B2") (pinfunction "7_B2") (pintype "passive"))
      (node (ref "SEL7") (pin "A") (pinfunction "A_A") (pintype "passive"))
    )
    (net (code "62") (name "Net-(R15-8)") (class "Default")
      (node (ref "R15") (pin "A2") (pinfunction "8_A2") (pintype "passive"))
      (node (ref "SEL8") (pin "A") (pinfunction "A_A") (pintype "passive"))
    )
    (net (code "63") (name "Net-(T1-D)") (class "Default")
      (node (ref "R1") (pin "1") (pinfunction "1_1") (pintype "passive"))
      (node (ref "R2") (pin "1") (pinfunction "1_1") (pintype "passive"))
      (node (ref "R3") (pin "1") (pinfunction "1_1") (pintype "passive"))
      (node (ref "T1") (pin "3") (pinfunction "D_3") (pintype "passive"))
    )
    (net (code "64") (name "unconnected-(CON1-Pad1)") (class "Default")
      (node (ref "CON1") (pin "1") (pinfunction "1_1") (pintype "bidirectional"))
    )
    (net (code "65") (name "unconnected-(CON1-Pad2)") (class "Default")
      (node (ref "CON1") (pin "2") (pinfunction "2_2") (pintype "bidirectional"))
    )
    (net (code "66") (name "unconnected-(CON1-Pad3)") (class "Default")
      (node (ref "CON1") (pin "3") (pinfunction "3_3") (pintype "bidirectional"))
    )
    (net (code "67") (name "unconnected-(CON1-Pad4)") (class "Default")
      (node (ref "CON1") (pin "4") (pinfunction "4_4") (pintype "bidirectional"))
    )
    (net (code "68") (name "unconnected-(CON1-Pad8)") (class "Default")
      (node (ref "CON1") (pin "8") (pinfunction "8_8") (pintype "bidirectional"))
    )
    (net (code "69") (name "unconnected-(IC1-INTA-Pad16)") (class "Default")
      (node (ref "IC1") (pin "16") (pinfunction "INTA_16") (pintype "bidirectional"))
    )
    (net (code "70") (name "unconnected-(IC1-INTB-Pad15)") (class "Default")
      (node (ref "IC1") (pin "15") (pinfunction "INTB_15") (pintype "bidirectional"))
    )
    (net (code "71") (name "unconnected-(IC1-IO2.3-Pad28)") (class "Default")
      (node (ref "IC1") (pin "28") (pinfunction "IO2.3_28") (pintype "bidirectional"))
    )
    (net (code "72") (name "unconnected-(IC1-IO2.4-Pad1)") (class "Default")
      (node (ref "IC1") (pin "1") (pinfunction "IO2.4_1") (pintype "bidirectional"))
    )
    (net (code "73") (name "unconnected-(IC1-IO2.5-Pad2)") (class "Default")
      (node (ref "IC1") (pin "2") (pinfunction "IO2.5_2") (pintype "bidirectional"))
    )
    (net (code "74") (name "unconnected-(IC1-IO2.6-Pad3)") (class "Default")
      (node (ref "IC1") (pin "3") (pinfunction "IO2.6_3") (pintype "bidirectional"))
    )
    (net (code "75") (name "unconnected-(IC1-IO2.7-Pad4)") (class "Default")
      (node (ref "IC1") (pin "4") (pinfunction "IO2.7_4") (pintype "bidirectional"))
    )
    (net (code "76") (name "unconnected-(IC2-INTA-Pad16)") (class "Default")
      (node (ref "IC2") (pin "16") (pinfunction "INTA_16") (pintype "bidirectional"))
    )
    (net (code "77") (name "unconnected-(IC2-INTB-Pad15)") (class "Default")
      (node (ref "IC2") (pin "15") (pinfunction "INTB_15") (pintype "bidirectional"))
    )
    (net (code "78") (name "unconnected-(IC2-IO2.0-Pad25)") (class "Default")
      (node (ref "IC2") (pin "25") (pinfunction "IO2.0_25") (pintype "bidirectional"))
    )
    (net (code "79") (name "unconnected-(IC2-IO2.1-Pad26)") (class "Default")
      (node (ref "IC2") (pin "26") (pinfunction "IO2.1_26") (pintype "bidirectional"))
    )
    (net (code "80") (name "unconnected-(IC2-IO2.2-Pad27)") (class "Default")
      (node (ref "IC2") (pin "27") (pinfunction "IO2.2_27") (pintype "bidirectional"))
    )
    (net (code "81") (name "unconnected-(IC2-IO2.3-Pad28)") (class "Default")
      (node (ref "IC2") (pin "28") (pinfunction "IO2.3_28") (pintype "bidirectional"))
    )
    (net (code "82") (name "unconnected-(IC2-IO2.4-Pad1)") (class "Default")
      (node (ref "IC2") (pin "1") (pinfunction "IO2.4_1") (pintype "bidirectional"))
    )
    (net (code "83") (name "unconnected-(IC2-IO2.5-Pad2)") (class "Default")
      (node (ref "IC2") (pin "2") (pinfunction "IO2.5_2") (pintype "bidirectional"))
    )
    (net (code "84") (name "unconnected-(IC2-IO2.6-Pad3)") (class "Default")
      (node (ref "IC2") (pin "3") (pinfunction "IO2.6_3") (pintype "bidirectional"))
    )
    (net (code "85") (name "unconnected-(IC2-IO2.7-Pad4)") (class "Default")
      (node (ref "IC2") (pin "4") (pinfunction "IO2.7_4") (pintype "bidirectional"))
    )
  )
)
